# ir2104_V1_1.net
KiCad netlist of a schematic drawn in EasyEDA Pro
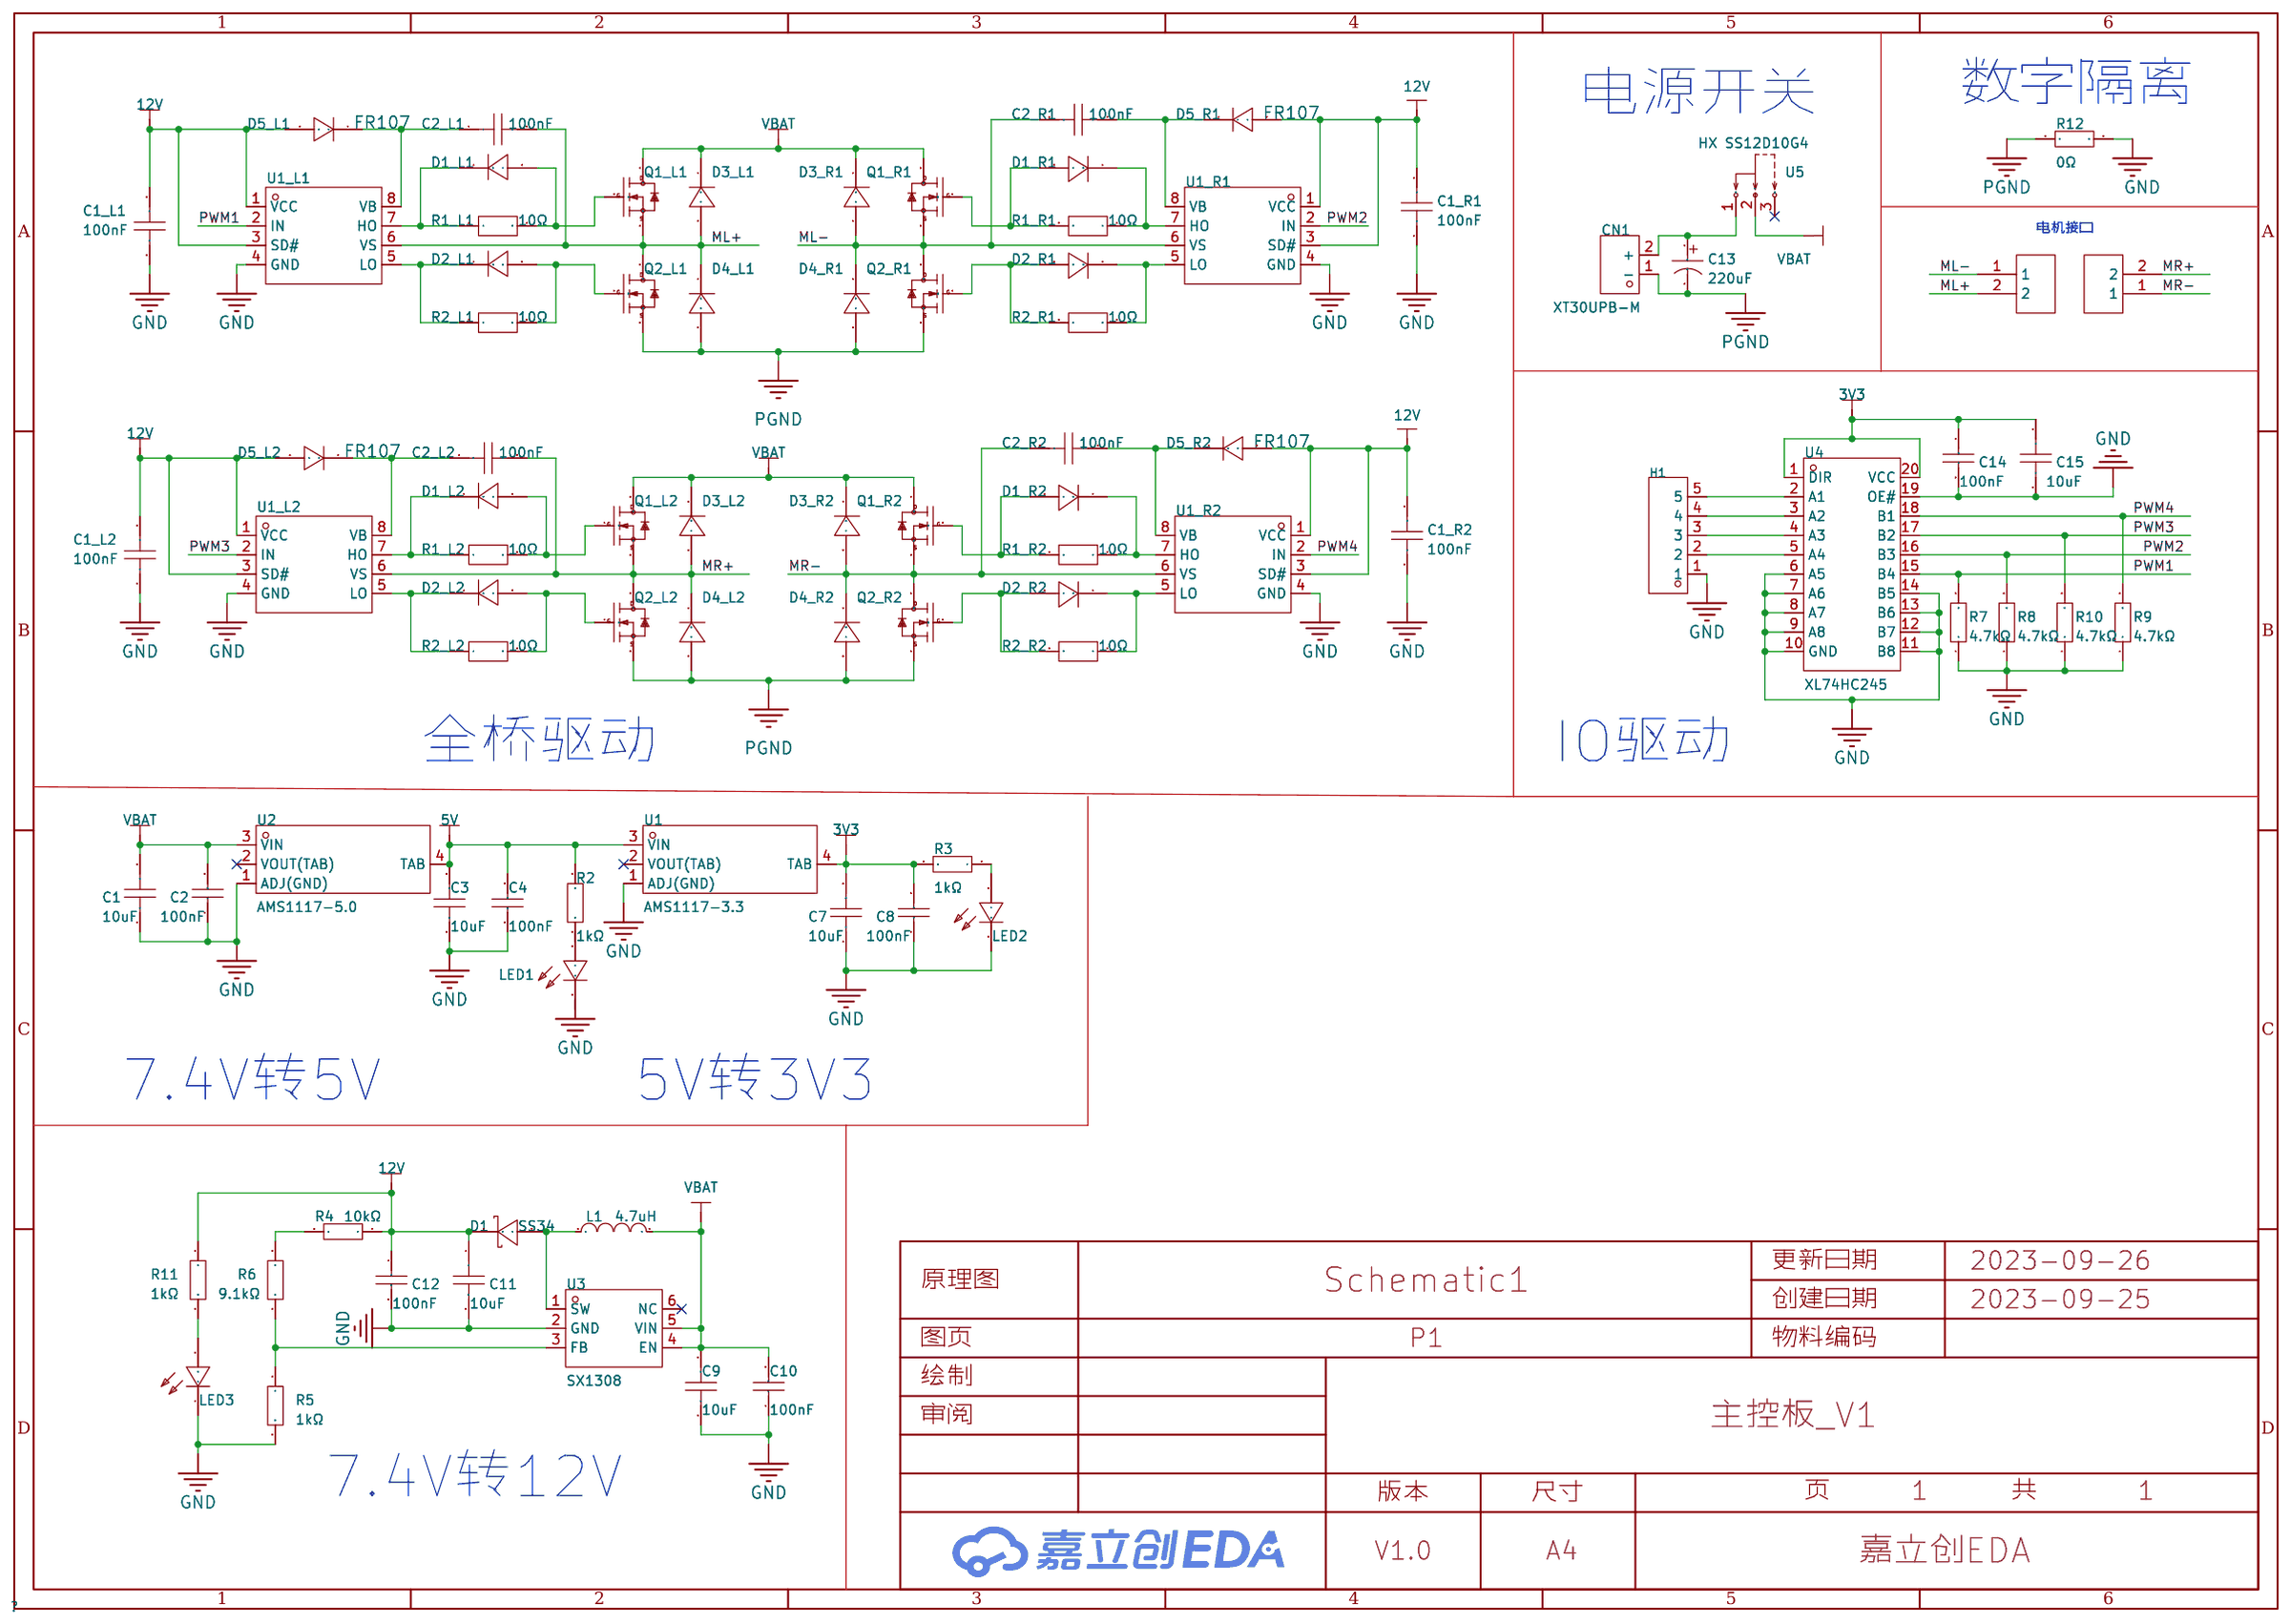
[diagram p0: schematic sheet]

(export (version "E")
  (design (tool "Eeschema 10.0.6"))
  (components
    (comp (ref "C1")
      (value "10uF")
      (footprint "easyedapro:C0603")
      (description "容值:10uF;精度:±20%;额定电压:25V;材质(温度系数):X5R;")
      (fields
        (field (name "Manufacturer Part") "CL10A106MA8NRNC")
        (field (name "Manufacturer") "SAMSUNG(三星)")
      )
      (libsource (lib "easyedapro") (part "CL10A106MA8NRNC"))
    )
    (comp (ref "C1_L1")
      (value "100nF")
      (footprint "easyedapro:C0603")
      (description "容值:100nF;精度:±10%;额定电压:50V;材质(温度系数):X7R;")
      (fields
        (field (name "Manufacturer Part") "CL10B104KB8NNNC")
        (field (name "Manufacturer") "SAMSUNG(三星)")
      )
      (libsource (lib "easyedapro") (part "CL10B104KB8NNNC"))
    )
    (comp (ref "C1_L2")
      (value "100nF")
      (footprint "easyedapro:C0603")
      (description "容值:100nF;精度:±10%;额定电压:50V;材质(温度系数):X7R;")
      (fields
        (field (name "Manufacturer Part") "CL10B104KB8NNNC")
        (field (name "Manufacturer") "SAMSUNG(三星)")
      )
      (libsource (lib "easyedapro") (part "CL10B104KB8NNNC"))
    )
    (comp (ref "C1_R1")
      (value "100nF")
      (footprint "easyedapro:C0603")
      (description "容值:100nF;精度:±10%;额定电压:50V;材质(温度系数):X7R;")
      (fields
        (field (name "Manufacturer Part") "CL10B104KB8NNNC")
        (field (name "Manufacturer") "SAMSUNG(三星)")
      )
      (libsource (lib "easyedapro") (part "CL10B104KB8NNNC"))
    )
    (comp (ref "C1_R2")
      (value "100nF")
      (footprint "easyedapro:C0603")
      (description "容值:100nF;精度:±10%;额定电压:50V;材质(温度系数):X7R;")
      (fields
        (field (name "Manufacturer Part") "CL10B104KB8NNNC")
        (field (name "Manufacturer") "SAMSUNG(三星)")
      )
      (libsource (lib "easyedapro") (part "CL10B104KB8NNNC"))
    )
    (comp (ref "C2")
      (value "100nF")
      (footprint "easyedapro:C0603")
      (description "容值:100nF;精度:±10%;额定电压:50V;材质(温度系数):X7R;")
      (fields (field (name "Manufacturer Part") "0603B104K500NT") (field (name "Manufacturer") "FH(风华)"))
      (libsource (lib "easyedapro") (part "0603B104K500NT"))
    )
    (comp (ref "C2_L1")
      (value "100nF")
      (footprint "easyedapro:C0603")
      (description "容值:100nF;精度:±10%;额定电压:50V;材质(温度系数):X7R;")
      (fields
        (field (name "Manufacturer Part") "CL10B104KB8NNNC")
        (field (name "Manufacturer") "SAMSUNG(三星)")
      )
      (libsource (lib "easyedapro") (part "CL10B104KB8NNNC"))
    )
    (comp (ref "C2_L2")
      (value "100nF")
      (footprint "easyedapro:C0603")
      (description "容值:100nF;精度:±10%;额定电压:50V;材质(温度系数):X7R;")
      (fields
        (field (name "Manufacturer Part") "CL10B104KB8NNNC")
        (field (name "Manufacturer") "SAMSUNG(三星)")
      )
      (libsource (lib "easyedapro") (part "CL10B104KB8NNNC"))
    )
    (comp (ref "C2_R1")
      (value "100nF")
      (footprint "easyedapro:C0603")
      (description "容值:100nF;精度:±10%;额定电压:50V;材质(温度系数):X7R;")
      (fields
        (field (name "Manufacturer Part") "CL10B104KB8NNNC")
        (field (name "Manufacturer") "SAMSUNG(三星)")
      )
      (libsource (lib "easyedapro") (part "CL10B104KB8NNNC"))
    )
    (comp (ref "C2_R2")
      (value "100nF")
      (footprint "easyedapro:C0603")
      (description "容值:100nF;精度:±10%;额定电压:50V;材质(温度系数):X7R;")
      (fields
        (field (name "Manufacturer Part") "CL10B104KB8NNNC")
        (field (name "Manufacturer") "SAMSUNG(三星)")
      )
      (libsource (lib "easyedapro") (part "CL10B104KB8NNNC"))
    )
    (comp (ref "C3")
      (value "10uF")
      (footprint "easyedapro:C0603")
      (description "容值:10uF;精度:±20%;额定电压:25V;材质(温度系数):X5R;")
      (fields
        (field (name "Manufacturer Part") "CL10A106MA8NRNC")
        (field (name "Manufacturer") "SAMSUNG(三星)")
      )
      (libsource (lib "easyedapro") (part "CL10A106MA8NRNC"))
    )
    (comp (ref "C4")
      (value "100nF")
      (footprint "easyedapro:C0603")
      (description "容值:100nF;精度:±10%;额定电压:50V;材质(温度系数):X7R;")
      (fields (field (name "Manufacturer Part") "0603B104K500NT") (field (name "Manufacturer") "FH(风华)"))
      (libsource (lib "easyedapro") (part "0603B104K500NT"))
    )
    (comp (ref "C7")
      (value "10uF")
      (footprint "easyedapro:C0603")
      (description "容值:10uF;精度:±20%;额定电压:25V;材质(温度系数):X5R;")
      (fields
        (field (name "Manufacturer Part") "CL10A106MA8NRNC")
        (field (name "Manufacturer") "SAMSUNG(三星)")
      )
      (libsource (lib "easyedapro") (part "CL10A106MA8NRNC"))
    )
    (comp (ref "C8")
      (value "100nF")
      (footprint "easyedapro:C0603")
      (description "容值:100nF;精度:±10%;额定电压:50V;材质(温度系数):X7R;")
      (fields (field (name "Manufacturer Part") "0603B104K500NT") (field (name "Manufacturer") "FH(风华)"))
      (libsource (lib "easyedapro") (part "0603B104K500NT"))
    )
    (comp (ref "C9")
      (value "10uF")
      (footprint "easyedapro:C0603")
      (description "容值:10uF;精度:±20%;额定电压:25V;材质(温度系数):X5R;")
      (fields
        (field (name "Manufacturer Part") "CL10A106MA8NRNC")
        (field (name "Manufacturer") "SAMSUNG(三星)")
      )
      (libsource (lib "easyedapro") (part "CL10A106MA8NRNC"))
    )
    (comp (ref "C10")
      (value "100nF")
      (footprint "easyedapro:C0603")
      (description "容值:100nF;精度:±10%;额定电压:50V;材质(温度系数):X7R;")
      (fields (field (name "Manufacturer Part") "0603B104K500NT") (field (name "Manufacturer") "FH(风华)"))
      (libsource (lib "easyedapro") (part "0603B104K500NT"))
    )
    (comp (ref "C11")
      (value "10uF")
      (footprint "easyedapro:C0603")
      (description "容值:10uF;精度:±20%;额定电压:25V;材质(温度系数):X5R;")
      (fields
        (field (name "Manufacturer Part") "CL10A106MA8NRNC")
        (field (name "Manufacturer") "SAMSUNG(三星)")
      )
      (libsource (lib "easyedapro") (part "CL10A106MA8NRNC"))
    )
    (comp (ref "C12")
      (value "100nF")
      (footprint "easyedapro:C0603")
      (description "容值:100nF;精度:±10%;额定电压:50V;材质(温度系数):X7R;")
      (fields (field (name "Manufacturer Part") "0603B104K500NT") (field (name "Manufacturer") "FH(风华)"))
      (libsource (lib "easyedapro") (part "0603B104K500NT"))
    )
    (comp (ref "C13")
      (value "220uF")
      (footprint "easyedapro:CAP-TH_BD8.0-P3.50-D0.6-FD")
      (description "容值:220uF;精度:±20%;额定电压:35V;纹波电流:-;等效串联电阻:-;")
      (fields
        (field (name "Manufacturer Part") "KM227M035F12RR0VH2FP0")
        (field (name "Manufacturer") "CX(承兴)")
      )
      (libsource (lib "easyedapro") (part "220uf/35V"))
    )
    (comp (ref "C14")
      (value "100nF")
      (footprint "easyedapro:C0603")
      (description "容值:100nF;精度:±10%;额定电压:50V;材质(温度系数):X7R;")
      (fields (field (name "Manufacturer Part") "0603B104K500NT") (field (name "Manufacturer") "FH(风华)"))
      (libsource (lib "easyedapro") (part "0603B104K500NT"))
    )
    (comp (ref "C15")
      (value "10uF")
      (footprint "easyedapro:C0603")
      (description "容值:10uF;精度:±20%;额定电压:25V;材质(温度系数):X5R;")
      (fields
        (field (name "Manufacturer Part") "CL10A106MA8NRNC")
        (field (name "Manufacturer") "SAMSUNG(三星)")
      )
      (libsource (lib "easyedapro") (part "CL10A106MA8NRNC"))
    )
    (comp (ref "CN1")
      (value "XT30UPB-M")
      (footprint "easyedapro:CONN-TH_XT30UPB-M")
      (fields (field (name "Manufacturer") "AMASS(艾迈斯)"))
      (libsource (lib "easyedapro") (part "XT30UPB-M"))
    )
    (comp (ref "D1")
      (value "SS34")
      (footprint "easyedapro:SMA_L4.3-W2.6-LS5.2-RD")
      (description "二极管配置:独立式;直流反向耐压(Vr):40V;平均整流电流(Io):3A;正向压降(Vf):550mV@3A;")
      (fields (field (name "Manufacturer") "MDD"))
      (libsource (lib "easyedapro") (part "SS34_C8678"))
    )
    (comp (ref "D1_L1")
      (value "US1M")
      (footprint "easyedapro:SMA_L4.4-W2.8-LS5.4-RD")
      (fields (field (name "Manufacturer") "MDD"))
      (libsource (lib "easyedapro") (part "US1MG_C412437"))
    )
    (comp (ref "D1_L2")
      (value "US1M")
      (footprint "easyedapro:SMA_L4.4-W2.8-LS5.4-RD")
      (fields (field (name "Manufacturer") "MDD"))
      (libsource (lib "easyedapro") (part "US1MG_C412437"))
    )
    (comp (ref "D1_R1")
      (value "US1M")
      (footprint "easyedapro:SMA_L4.4-W2.8-LS5.4-RD")
      (fields (field (name "Manufacturer") "MDD"))
      (libsource (lib "easyedapro") (part "US1MG_C412437"))
    )
    (comp (ref "D1_R2")
      (value "US1M")
      (footprint "easyedapro:SMA_L4.4-W2.8-LS5.4-RD")
      (fields (field (name "Manufacturer") "MDD"))
      (libsource (lib "easyedapro") (part "US1MG_C412437"))
    )
    (comp (ref "D2_L1")
      (value "US1M")
      (footprint "easyedapro:SMA_L4.4-W2.8-LS5.4-RD")
      (fields (field (name "Manufacturer") "MDD"))
      (libsource (lib "easyedapro") (part "US1MG_C412437"))
    )
    (comp (ref "D2_L2")
      (value "US1M")
      (footprint "easyedapro:SMA_L4.4-W2.8-LS5.4-RD")
      (fields (field (name "Manufacturer") "MDD"))
      (libsource (lib "easyedapro") (part "US1MG_C412437"))
    )
    (comp (ref "D2_R1")
      (value "US1M")
      (footprint "easyedapro:SMA_L4.4-W2.8-LS5.4-RD")
      (fields (field (name "Manufacturer") "MDD"))
      (libsource (lib "easyedapro") (part "US1MG_C412437"))
    )
    (comp (ref "D2_R2")
      (value "US1M")
      (footprint "easyedapro:SMA_L4.4-W2.8-LS5.4-RD")
      (fields (field (name "Manufacturer") "MDD"))
      (libsource (lib "easyedapro") (part "US1MG_C412437"))
    )
    (comp (ref "D3_L1")
      (value "US1M")
      (footprint "easyedapro:SMA_L4.4-W2.8-LS5.4-RD")
      (fields (field (name "Manufacturer") "MDD"))
      (libsource (lib "easyedapro") (part "US1MG_C412437"))
    )
    (comp (ref "D3_L2")
      (value "US1M")
      (footprint "easyedapro:SMA_L4.4-W2.8-LS5.4-RD")
      (fields (field (name "Manufacturer") "MDD"))
      (libsource (lib "easyedapro") (part "US1MG_C412437"))
    )
    (comp (ref "D3_R1")
      (value "US1M")
      (footprint "easyedapro:SMA_L4.4-W2.8-LS5.4-RD")
      (fields (field (name "Manufacturer") "MDD"))
      (libsource (lib "easyedapro") (part "US1MG_C412437"))
    )
    (comp (ref "D3_R2")
      (value "US1M")
      (footprint "easyedapro:SMA_L4.4-W2.8-LS5.4-RD")
      (fields (field (name "Manufacturer") "MDD"))
      (libsource (lib "easyedapro") (part "US1MG_C412437"))
    )
    (comp (ref "D4_L1")
      (value "US1M")
      (footprint "easyedapro:SMA_L4.4-W2.8-LS5.4-RD")
      (fields (field (name "Manufacturer") "MDD"))
      (libsource (lib "easyedapro") (part "US1MG_C412437"))
    )
    (comp (ref "D4_L2")
      (value "US1M")
      (footprint "easyedapro:SMA_L4.4-W2.8-LS5.4-RD")
      (fields (field (name "Manufacturer") "MDD"))
      (libsource (lib "easyedapro") (part "US1MG_C412437"))
    )
    (comp (ref "D4_R1")
      (value "US1M")
      (footprint "easyedapro:SMA_L4.4-W2.8-LS5.4-RD")
      (fields (field (name "Manufacturer") "MDD"))
      (libsource (lib "easyedapro") (part "US1MG_C412437"))
    )
    (comp (ref "D4_R2")
      (value "US1M")
      (footprint "easyedapro:SMA_L4.4-W2.8-LS5.4-RD")
      (fields (field (name "Manufacturer") "MDD"))
      (libsource (lib "easyedapro") (part "US1MG_C412437"))
    )
    (comp (ref "D5_L1")
      (value "FR107")
      (footprint "easyedapro:SOD-123_L2.8-W1.8-LS3.7-RD")
      (fields (field (name "Manufacturer") "BORN(伯恩半导体)"))
      (libsource (lib "easyedapro") (part "FR107_C511885"))
    )
    (comp (ref "D5_L2")
      (value "FR107")
      (footprint "easyedapro:SOD-123_L2.8-W1.8-LS3.7-RD")
      (fields (field (name "Manufacturer") "BORN(伯恩半导体)"))
      (libsource (lib "easyedapro") (part "FR107_C511885"))
    )
    (comp (ref "D5_R1")
      (value "FR107")
      (footprint "easyedapro:SOD-123_L2.8-W1.8-LS3.7-RD")
      (fields (field (name "Manufacturer") "BORN(伯恩半导体)"))
      (libsource (lib "easyedapro") (part "FR107_C511885"))
    )
    (comp (ref "D5_R2")
      (value "FR107")
      (footprint "easyedapro:SOD-123_L2.8-W1.8-LS3.7-RD")
      (fields (field (name "Manufacturer") "BORN(伯恩半导体)"))
      (libsource (lib "easyedapro") (part "FR107_C511885"))
    )
    (comp (ref "H1")
      (value "PZ254V-11-05P")
      (footprint "easyedapro:HDR-TH_5P-P2.54-V-M")
      (fields (field (name "Manufacturer") "XFCN(兴飞)"))
      (libsource (lib "easyedapro") (part "PZ254V-11-05P"))
    )
    (comp (ref "L1")
      (value "4.7uH")
      (footprint "easyedapro:IND-SMD_L5.4-W5.2_FXL0530")
      (description "电感值:4.7uH;精度:±20%;额定电流:4.5A;饱和电流(Isat):5A;")
      (fields (field (name "Manufacturer Part") "FXL0530-4R7-M") (field (name "Manufacturer") "cjiang(长江微电)"))
      (libsource (lib "easyedapro") (part "FXL0530-4R7-M"))
    )
    (comp (ref "LED1")
      (value "NCD0603R1")
      (footprint "easyedapro:LED0603-RD_RED")
      (description "发光颜色:红灯;")
      (fields (field (name "Manufacturer") "国星光电"))
      (libsource (lib "easyedapro") (part "FC-DA1608HRK-620D"))
    )
    (comp (ref "LED2")
      (value "NCD0603R1")
      (footprint "easyedapro:LED0603-RD_RED")
      (description "发光颜色:红灯;")
      (fields (field (name "Manufacturer") "国星光电"))
      (libsource (lib "easyedapro") (part "FC-DA1608HRK-620D"))
    )
    (comp (ref "LED3")
      (value "NCD0603R1")
      (footprint "easyedapro:LED0603-RD_RED")
      (description "发光颜色:红灯;")
      (fields (field (name "Manufacturer") "国星光电"))
      (libsource (lib "easyedapro") (part "FC-DA1608HRK-620D"))
    )
    (comp (ref "P1")
      (value "WJ500V-5.08-2P")
      (footprint "easyedapro:CONN-TH_2P-P5.00_WJ500V-5.08-2P")
      (fields (field (name "Manufacturer") "KANGNEX(康奈克斯电气)"))
      (libsource (lib "easyedapro") (part "WJ500V-5.08-2P-14-00A"))
    )
    (comp (ref "P2")
      (value "WJ500V-5.08-2P")
      (footprint "easyedapro:CONN-TH_2P-P5.00_WJ500V-5.08-2P")
      (fields (field (name "Manufacturer") "KANGNEX(康奈克斯电气)"))
      (libsource (lib "easyedapro") (part "WJ500V-5.08-2P-14-00A"))
    )
    (comp (ref "Q1_L1")
      (value "IRFR3607TRPBF")
      (footprint "easyedapro:TO-252-3_L6.5-W5.8-P4.58-BL")
      (fields (field (name "Manufacturer") "Infineon(英飞凌)"))
      (libsource (lib "easyedapro") (part "IRFR3607TRPBF"))
    )
    (comp (ref "Q1_L2")
      (value "IRFR3607TRPBF")
      (footprint "easyedapro:TO-252-3_L6.5-W5.8-P4.58-BL")
      (fields (field (name "Manufacturer") "Infineon(英飞凌)"))
      (libsource (lib "easyedapro") (part "IRFR3607TRPBF"))
    )
    (comp (ref "Q1_R1")
      (value "IRFR3607TRPBF")
      (footprint "easyedapro:TO-252-3_L6.5-W5.8-P4.58-BL")
      (fields (field (name "Manufacturer") "Infineon(英飞凌)"))
      (libsource (lib "easyedapro") (part "IRFR3607TRPBF"))
    )
    (comp (ref "Q1_R2")
      (value "IRFR3607TRPBF")
      (footprint "easyedapro:TO-252-3_L6.5-W5.8-P4.58-BL")
      (fields (field (name "Manufacturer") "Infineon(英飞凌)"))
      (libsource (lib "easyedapro") (part "IRFR3607TRPBF"))
    )
    (comp (ref "Q2_L1")
      (value "IRFR3607TRPBF")
      (footprint "easyedapro:TO-252-3_L6.5-W5.8-P4.58-BL")
      (fields (field (name "Manufacturer") "Infineon(英飞凌)"))
      (libsource (lib "easyedapro") (part "IRFR3607TRPBF"))
    )
    (comp (ref "Q2_L2")
      (value "IRFR3607TRPBF")
      (footprint "easyedapro:TO-252-3_L6.5-W5.8-P4.58-BL")
      (fields (field (name "Manufacturer") "Infineon(英飞凌)"))
      (libsource (lib "easyedapro") (part "IRFR3607TRPBF"))
    )
    (comp (ref "Q2_R1")
      (value "IRFR3607TRPBF")
      (footprint "easyedapro:TO-252-3_L6.5-W5.8-P4.58-BL")
      (fields (field (name "Manufacturer") "Infineon(英飞凌)"))
      (libsource (lib "easyedapro") (part "IRFR3607TRPBF"))
    )
    (comp (ref "Q2_R2")
      (value "IRFR3607TRPBF")
      (footprint "easyedapro:TO-252-3_L6.5-W5.8-P4.58-BL")
      (fields (field (name "Manufacturer") "Infineon(英飞凌)"))
      (libsource (lib "easyedapro") (part "IRFR3607TRPBF"))
    )
    (comp (ref "R1_L1")
      (value "10Ω")
      (footprint "easyedapro:R0603")
      (description "阻值:10Ω;精度:±0.5%;功率:250mW;")
      (fields (field (name "Manufacturer Part") "ERJUP3D10R0V") (field (name "Manufacturer") "PANASONIC(松下)"))
      (libsource (lib "easyedapro") (part "ERJUP3D10R0V"))
    )
    (comp (ref "R1_L2")
      (value "10Ω")
      (footprint "easyedapro:R0603")
      (description "阻值:10Ω;精度:±0.5%;功率:250mW;")
      (fields (field (name "Manufacturer Part") "ERJUP3D10R0V") (field (name "Manufacturer") "PANASONIC(松下)"))
      (libsource (lib "easyedapro") (part "ERJUP3D10R0V"))
    )
    (comp (ref "R1_R1")
      (value "10Ω")
      (footprint "easyedapro:R0603")
      (description "阻值:10Ω;精度:±0.5%;功率:250mW;")
      (fields (field (name "Manufacturer Part") "ERJUP3D10R0V") (field (name "Manufacturer") "PANASONIC(松下)"))
      (libsource (lib "easyedapro") (part "ERJUP3D10R0V"))
    )
    (comp (ref "R1_R2")
      (value "10Ω")
      (footprint "easyedapro:R0603")
      (description "阻值:10Ω;精度:±0.5%;功率:250mW;")
      (fields (field (name "Manufacturer Part") "ERJUP3D10R0V") (field (name "Manufacturer") "PANASONIC(松下)"))
      (libsource (lib "easyedapro") (part "ERJUP3D10R0V"))
    )
    (comp (ref "R2")
      (value "1kΩ")
      (footprint "easyedapro:R0603")
      (description "电阻类型:厚膜电阻;阻值:1kΩ;精度:±1%;功率:100mW;")
      (fields
        (field (name "Manufacturer Part") "0603WAF1001T5E")
        (field (name "Manufacturer") "UNI-ROYAL(厚声)")
      )
      (libsource (lib "easyedapro") (part "0603WAF1001T5E"))
    )
    (comp (ref "R2_L1")
      (value "10Ω")
      (footprint "easyedapro:R0603")
      (description "阻值:10Ω;精度:±0.5%;功率:250mW;")
      (fields (field (name "Manufacturer Part") "ERJUP3D10R0V") (field (name "Manufacturer") "PANASONIC(松下)"))
      (libsource (lib "easyedapro") (part "ERJUP3D10R0V"))
    )
    (comp (ref "R2_L2")
      (value "10Ω")
      (footprint "easyedapro:R0603")
      (description "阻值:10Ω;精度:±0.5%;功率:250mW;")
      (fields (field (name "Manufacturer Part") "ERJUP3D10R0V") (field (name "Manufacturer") "PANASONIC(松下)"))
      (libsource (lib "easyedapro") (part "ERJUP3D10R0V"))
    )
    (comp (ref "R2_R1")
      (value "10Ω")
      (footprint "easyedapro:R0603")
      (description "阻值:10Ω;精度:±0.5%;功率:250mW;")
      (fields (field (name "Manufacturer Part") "ERJUP3D10R0V") (field (name "Manufacturer") "PANASONIC(松下)"))
      (libsource (lib "easyedapro") (part "ERJUP3D10R0V"))
    )
    (comp (ref "R2_R2")
      (value "10Ω")
      (footprint "easyedapro:R0603")
      (description "阻值:10Ω;精度:±0.5%;功率:250mW;")
      (fields (field (name "Manufacturer Part") "ERJUP3D10R0V") (field (name "Manufacturer") "PANASONIC(松下)"))
      (libsource (lib "easyedapro") (part "ERJUP3D10R0V"))
    )
    (comp (ref "R3")
      (value "1kΩ")
      (footprint "easyedapro:R0603")
      (description "电阻类型:厚膜电阻;阻值:1kΩ;精度:±1%;功率:100mW;")
      (fields
        (field (name "Manufacturer Part") "0603WAF1001T5E")
        (field (name "Manufacturer") "UNI-ROYAL(厚声)")
      )
      (libsource (lib "easyedapro") (part "0603WAF1001T5E"))
    )
    (comp (ref "R4")
      (value "10kΩ")
      (footprint "easyedapro:R0603")
      (description "电阻类型:薄膜电阻;阻值:10kΩ;精度:±0.1%;功率:100mW;")
      (fields (field (name "Manufacturer Part") "RT0603BRD0710KL") (field (name "Manufacturer") "YAGEO(国巨)"))
      (libsource (lib "easyedapro") (part "RT0603BRD0710KL"))
    )
    (comp (ref "R5")
      (value "1kΩ")
      (footprint "easyedapro:R0603")
      (description "电阻类型:薄膜电阻;阻值:1kΩ;精度:±0.1%;功率:100mW;")
      (fields (field (name "Manufacturer Part") "RT0603BRD071KL") (field (name "Manufacturer") "YAGEO(国巨)"))
      (libsource (lib "easyedapro") (part "RT0603BRD071KL"))
    )
    (comp (ref "R6")
      (value "9.1kΩ")
      (footprint "easyedapro:R0603")
      (description "电阻类型:薄膜电阻;阻值:9.1kΩ;精度:±0.1%;功率:100mW;")
      (fields (field (name "Manufacturer Part") "PTFR0603B9K10P9") (field (name "Manufacturer") "RESI(开步睿思）"))
      (libsource (lib "easyedapro") (part "PTFR0603B9K10P9"))
    )
    (comp (ref "R7")
      (value "4.7kΩ")
      (footprint "easyedapro:R0603")
      (description "电阻类型:厚膜电阻;阻值:4.7kΩ;精度:±1%;功率:100mW;")
      (fields
        (field (name "Manufacturer Part") "0603WAF4701T5E")
        (field (name "Manufacturer") "UNI-ROYAL(厚声)")
      )
      (libsource (lib "easyedapro") (part "0603WAF4701T5E"))
    )
    (comp (ref "R8")
      (value "4.7kΩ")
      (footprint "easyedapro:R0603")
      (description "电阻类型:厚膜电阻;阻值:4.7kΩ;精度:±1%;功率:100mW;")
      (fields
        (field (name "Manufacturer Part") "0603WAF4701T5E")
        (field (name "Manufacturer") "UNI-ROYAL(厚声)")
      )
      (libsource (lib "easyedapro") (part "0603WAF4701T5E"))
    )
    (comp (ref "R9")
      (value "4.7kΩ")
      (footprint "easyedapro:R0603")
      (description "电阻类型:厚膜电阻;阻值:4.7kΩ;精度:±1%;功率:100mW;")
      (fields
        (field (name "Manufacturer Part") "0603WAF4701T5E")
        (field (name "Manufacturer") "UNI-ROYAL(厚声)")
      )
      (libsource (lib "easyedapro") (part "0603WAF4701T5E"))
    )
    (comp (ref "R10")
      (value "4.7kΩ")
      (footprint "easyedapro:R0603")
      (description "电阻类型:厚膜电阻;阻值:4.7kΩ;精度:±1%;功率:100mW;")
      (fields
        (field (name "Manufacturer Part") "0603WAF4701T5E")
        (field (name "Manufacturer") "UNI-ROYAL(厚声)")
      )
      (libsource (lib "easyedapro") (part "0603WAF4701T5E"))
    )
    (comp (ref "R11")
      (value "1kΩ")
      (footprint "easyedapro:R0603")
      (description "电阻类型:厚膜电阻;阻值:1kΩ;精度:±1%;功率:100mW;")
      (fields
        (field (name "Manufacturer Part") "0603WAF1001T5E")
        (field (name "Manufacturer") "UNI-ROYAL(厚声)")
      )
      (libsource (lib "easyedapro") (part "0603WAF1001T5E"))
    )
    (comp (ref "R12")
      (value "0Ω")
      (footprint "easyedapro:R0805")
      (description "电阻类型:厚膜电阻;阻值:0Ω;精度:±1%;功率:125mW;")
      (fields
        (field (name "Manufacturer Part") "0805W8F0000T5E")
        (field (name "Manufacturer") "UNI-ROYAL(厚声)")
      )
      (libsource (lib "easyedapro") (part "0805W8F0000T5E"))
    )
    (comp (ref "U1")
      (value "AMS1117-3.3")
      (footprint "easyedapro:SOT-223-4_L6.5-W3.5-P2.30-LS7.0-BR")
      (description "输出类型:固定;输出极性:正;最大输入电压:18V;输出电压:3.3V;输出电流:1A;电源纹波抑制比(PSRR):60dB@(120Hz);")
      (fields (field (name "Manufacturer") "UMW(广东友台半导体)"))
      (libsource (lib "easyedapro") (part "AMS1117-3.3_C347222"))
    )
    (comp (ref "U1_L1")
      (value "EG2104")
      (footprint "easyedapro:SOP-8_L5.0-W4.0-P1.27-LS6.2-BL")
      (description "高性价比, 600V，半桥式Nmos预驱动器")
      (fields (field (name "Manufacturer") "EG(屹晶微)"))
      (libsource (lib "easyedapro") (part "EG2104"))
    )
    (comp (ref "U1_L2")
      (value "EG2104")
      (footprint "easyedapro:SOP-8_L5.0-W4.0-P1.27-LS6.2-BL")
      (description "高性价比, 600V，半桥式Nmos预驱动器")
      (fields (field (name "Manufacturer") "EG(屹晶微)"))
      (libsource (lib "easyedapro") (part "EG2104"))
    )
    (comp (ref "U1_R1")
      (value "EG2104")
      (footprint "easyedapro:SOP-8_L5.0-W4.0-P1.27-LS6.2-BL")
      (description "高性价比, 600V，半桥式Nmos预驱动器")
      (fields (field (name "Manufacturer") "EG(屹晶微)"))
      (libsource (lib "easyedapro") (part "EG2104"))
    )
    (comp (ref "U1_R2")
      (value "EG2104")
      (footprint "easyedapro:SOP-8_L5.0-W4.0-P1.27-LS6.2-BL")
      (description "高性价比, 600V，半桥式Nmos预驱动器")
      (fields (field (name "Manufacturer") "EG(屹晶微)"))
      (libsource (lib "easyedapro") (part "EG2104"))
    )
    (comp (ref "U2")
      (value "AMS1117-5.0")
      (footprint "easyedapro:SOT-223_L6.7-W3.5-P2.30-BR")
      (description "输出类型:固定;输出极性:正;最大输入电压:18V;输出电压:5V;输出电流:1A;电源纹波抑制比(PSRR):60dB@(120Hz);")
      (fields (field (name "Manufacturer") "UMW(广东友台半导体)"))
      (libsource (lib "easyedapro") (part "AMS1117-5.0_C347223"))
    )
    (comp (ref "U3")
      (value "SX1308")
      (footprint "easyedapro:SOT-23-6_L2.9-W1.6-P0.95-LS2.8-BL")
      (description "功能类型:升压型;同步整流:否;输出通道数:1;拓扑结构:升压式;输入电压:2V~24V;输出电压:28V;输出电流(最大值):-;开关频率:1.2MHz;")
      (fields (field (name "Manufacturer") "SX(硕芯科技)"))
      (libsource (lib "easyedapro") (part "SX1308"))
    )
    (comp (ref "U4")
      (value "XL74HC245")
      (footprint "easyedapro:SOP-20_L12.8-W7.5-P1.27-LS10.4-BL")
      (description "八路总线收发器")
      (fields (field (name "Manufacturer") "XINLUDA(信路达)"))
      (libsource (lib "easyedapro") (part "XL74HC245"))
    )
    (comp (ref "U5")
      (value "HX SS12D10G4")
      (footprint "easyedapro:SW-TH_SHOU-HAN_SS12D10G4")
      (fields (field (name "Manufacturer") "hanxia(韩下)"))
      (libsource (lib "easyedapro") (part "HX SS12D10G4"))
    )
  )
  (nets
    (net (code "1") (name "/ML+") (class "Default")
      (node (ref "C2_L1") (pin "2") (pinfunction "2_2") (pintype "input"))
      (node (ref "D3_L1") (pin "2") (pinfunction "A_2") (pintype "input"))
      (node (ref "D4_L1") (pin "1") (pinfunction "C_1") (pintype "input"))
      (node (ref "P1") (pin "2") (pinfunction "2_2") (pintype "input"))
      (node (ref "Q1_L1") (pin "3") (pinfunction "S_3") (pintype "input"))
      (node (ref "Q2_L1") (pin "2") (pinfunction "D_2") (pintype "input"))
      (node (ref "U1_L1") (pin "6") (pinfunction "VS_6") (pintype "input"))
    )
    (net (code "2") (name "/ML-") (class "Default")
      (node (ref "C2_R1") (pin "2") (pinfunction "2_2") (pintype "input"))
      (node (ref "D3_R1") (pin "2") (pinfunction "A_2") (pintype "input"))
      (node (ref "D4_R1") (pin "1") (pinfunction "C_1") (pintype "input"))
      (node (ref "P1") (pin "1") (pinfunction "1_1") (pintype "input"))
      (node (ref "Q1_R1") (pin "3") (pinfunction "S_3") (pintype "input"))
      (node (ref "Q2_R1") (pin "2") (pinfunction "D_2") (pintype "input"))
      (node (ref "U1_R1") (pin "6") (pinfunction "VS_6") (pintype "input"))
    )
    (net (code "3") (name "/MR+") (class "Default")
      (node (ref "C2_L2") (pin "2") (pinfunction "2_2") (pintype "input"))
      (node (ref "D3_L2") (pin "2") (pinfunction "A_2") (pintype "input"))
      (node (ref "D4_L2") (pin "1") (pinfunction "C_1") (pintype "input"))
      (node (ref "P2") (pin "2") (pinfunction "2_2") (pintype "input"))
      (node (ref "Q1_L2") (pin "3") (pinfunction "S_3") (pintype "input"))
      (node (ref "Q2_L2") (pin "2") (pinfunction "D_2") (pintype "input"))
      (node (ref "U1_L2") (pin "6") (pinfunction "VS_6") (pintype "input"))
    )
    (net (code "4") (name "/MR-") (class "Default")
      (node (ref "C2_R2") (pin "2") (pinfunction "2_2") (pintype "input"))
      (node (ref "D3_R2") (pin "2") (pinfunction "A_2") (pintype "input"))
      (node (ref "D4_R2") (pin "1") (pinfunction "C_1") (pintype "input"))
      (node (ref "P2") (pin "1") (pinfunction "1_1") (pintype "input"))
      (node (ref "Q1_R2") (pin "3") (pinfunction "S_3") (pintype "input"))
      (node (ref "Q2_R2") (pin "2") (pinfunction "D_2") (pintype "input"))
      (node (ref "U1_R2") (pin "6") (pinfunction "VS_6") (pintype "input"))
    )
    (net (code "5") (name "/PWM1") (class "Default")
      (node (ref "R7") (pin "2") (pinfunction "2_2") (pintype "input"))
      (node (ref "U1_L1") (pin "2") (pinfunction "IN_2") (pintype "input"))
      (node (ref "U4") (pin "15") (pinfunction "B4_15") (pintype "input"))
    )
    (net (code "6") (name "/PWM2") (class "Default")
      (node (ref "R8") (pin "2") (pinfunction "2_2") (pintype "input"))
      (node (ref "U1_R1") (pin "2") (pinfunction "IN_2") (pintype "input"))
      (node (ref "U4") (pin "16") (pinfunction "B3_16") (pintype "input"))
    )
    (net (code "7") (name "/PWM3") (class "Default")
      (node (ref "R10") (pin "2") (pinfunction "2_2") (pintype "input"))
      (node (ref "U1_L2") (pin "2") (pinfunction "IN_2") (pintype "input"))
      (node (ref "U4") (pin "17") (pinfunction "B2_17") (pintype "input"))
    )
    (net (code "8") (name "/PWM4") (class "Default")
      (node (ref "R9") (pin "2") (pinfunction "2_2") (pintype "input"))
      (node (ref "U1_R2") (pin "2") (pinfunction "IN_2") (pintype "input"))
      (node (ref "U4") (pin "18") (pinfunction "B1_18") (pintype "input"))
    )
    (net (code "9") (name "3V3") (class "Default")
      (node (ref "C14") (pin "1") (pinfunction "1_1") (pintype "input"))
      (node (ref "C15") (pin "1") (pinfunction "1_1") (pintype "input"))
      (node (ref "C7") (pin "2") (pinfunction "2_2") (pintype "input"))
      (node (ref "C8") (pin "2") (pinfunction "2_2") (pintype "input"))
      (node (ref "R3") (pin "2") (pinfunction "2_2") (pintype "input"))
      (node (ref "U1") (pin "4") (pinfunction "TAB_4") (pintype "input"))
      (node (ref "U4") (pin "1") (pinfunction "DIR_1") (pintype "input"))
      (node (ref "U4") (pin "20") (pinfunction "VCC_20") (pintype "input"))
    )
    (net (code "10") (name "5V") (class "Default")
      (node (ref "C3") (pin "2") (pinfunction "2_2") (pintype "input"))
      (node (ref "C4") (pin "2") (pinfunction "2_2") (pintype "input"))
      (node (ref "R2") (pin "1") (pinfunction "1_1") (pintype "input"))
      (node (ref "U1") (pin "3") (pinfunction "VIN_3") (pintype "input"))
      (node (ref "U2") (pin "4") (pinfunction "TAB_4") (pintype "input"))
    )
    (net (code "11") (name "12V") (class "Default")
      (node (ref "C11") (pin "1") (pinfunction "1_1") (pintype "input"))
      (node (ref "C12") (pin "1") (pinfunction "1_1") (pintype "input"))
      (node (ref "C1_L1") (pin "2") (pinfunction "2_2") (pintype "input"))
      (node (ref "C1_L2") (pin "2") (pinfunction "2_2") (pintype "input"))
      (node (ref "C1_R1") (pin "2") (pinfunction "2_2") (pintype "input"))
      (node (ref "C1_R2") (pin "2") (pinfunction "2_2") (pintype "input"))
      (node (ref "D1") (pin "1") (pinfunction "K_1") (pintype "input"))
      (node (ref "D5_L1") (pin "2") (pinfunction "A_2") (pintype "input"))
      (node (ref "D5_L2") (pin "2") (pinfunction "A_2") (pintype "input"))
      (node (ref "D5_R1") (pin "2") (pinfunction "A_2") (pintype "input"))
      (node (ref "D5_R2") (pin "2") (pinfunction "A_2") (pintype "input"))
      (node (ref "R11") (pin "1") (pinfunction "1_1") (pintype "input"))
      (node (ref "R4") (pin "1") (pinfunction "1_1") (pintype "input"))
      (node (ref "U1_L1") (pin "1") (pinfunction "VCC_1") (pintype "input"))
      (node (ref "U1_L1") (pin "3") (pinfunction "SD#_3") (pintype "input"))
      (node (ref "U1_L2") (pin "1") (pinfunction "VCC_1") (pintype "input"))
      (node (ref "U1_L2") (pin "3") (pinfunction "SD#_3") (pintype "input"))
      (node (ref "U1_R1") (pin "1") (pinfunction "VCC_1") (pintype "input"))
      (node (ref "U1_R1") (pin "3") (pinfunction "SD#_3") (pintype "input"))
      (node (ref "U1_R2") (pin "1") (pinfunction "VCC_1") (pintype "input"))
      (node (ref "U1_R2") (pin "3") (pinfunction "SD#_3") (pintype "input"))
    )
    (net (code "12") (name "GND") (class "Default")
      (node (ref "C1") (pin "1") (pinfunction "1_1") (pintype "input"))
      (node (ref "C10") (pin "1") (pinfunction "1_1") (pintype "input"))
      (node (ref "C11") (pin "2") (pinfunction "2_2") (pintype "input"))
      (node (ref "C12") (pin "2") (pinfunction "2_2") (pintype "input"))
      (node (ref "C14") (pin "2") (pinfunction "2_2") (pintype "input"))
      (node (ref "C15") (pin "2") (pinfunction "2_2") (pintype "input"))
      (node (ref "C1_L1") (pin "1") (pinfunction "1_1") (pintype "input"))
      (node (ref "C1_L2") (pin "1") (pinfunction "1_1") (pintype "input"))
      (node (ref "C1_R1") (pin "1") (pinfunction "1_1") (pintype "input"))
      (node (ref "C1_R2") (pin "1") (pinfunction "1_1") (pintype "input"))
      (node (ref "C2") (pin "1") (pinfunction "1_1") (pintype "input"))
      (node (ref "C3") (pin "1") (pinfunction "1_1") (pintype "input"))
      (node (ref "C4") (pin "1") (pinfunction "1_1") (pintype "input"))
      (node (ref "C7") (pin "1") (pinfunction "1_1") (pintype "input"))
      (node (ref "C8") (pin "1") (pinfunction "1_1") (pintype "input"))
      (node (ref "C9") (pin "1") (pinfunction "1_1") (pintype "input"))
      (node (ref "H1") (pin "1") (pinfunction "1_1") (pintype "input"))
      (node (ref "LED1") (pin "1") (pinfunction "K_1") (pintype "input"))
      (node (ref "LED2") (pin "1") (pinfunction "K_1") (pintype "input"))
      (node (ref "LED3") (pin "1") (pinfunction "K_1") (pintype "input"))
      (node (ref "R10") (pin "1") (pinfunction "1_1") (pintype "input"))
      (node (ref "R12") (pin "2") (pinfunction "2_2") (pintype "input"))
      (node (ref "R5") (pin "2") (pinfunction "2_2") (pintype "input"))
      (node (ref "R7") (pin "1") (pinfunction "1_1") (pintype "input"))
      (node (ref "R8") (pin "1") (pinfunction "1_1") (pintype "input"))
      (node (ref "R9") (pin "1") (pinfunction "1_1") (pintype "input"))
      (node (ref "U1") (pin "1") (pinfunction "ADJ(GND)_1") (pintype "input"))
      (node (ref "U1_L1") (pin "4") (pinfunction "GND_4") (pintype "input"))
      (node (ref "U1_L2") (pin "4") (pinfunction "GND_4") (pintype "input"))
      (node (ref "U1_R1") (pin "4") (pinfunction "GND_4") (pintype "input"))
      (node (ref "U1_R2") (pin "4") (pinfunction "GND_4") (pintype "input"))
      (node (ref "U2") (pin "1") (pinfunction "ADJ(GND)_1") (pintype "input"))
      (node (ref "U3") (pin "2") (pinfunction "GND_2") (pintype "input"))
      (node (ref "U4") (pin "10") (pinfunction "GND_10") (pintype "input"))
      (node (ref "U4") (pin "11") (pinfunction "B8_11") (pintype "input"))
      (node (ref "U4") (pin "12") (pinfunction "B7_12") (pintype "input"))
      (node (ref "U4") (pin "13") (pinfunction "B6_13") (pintype "input"))
      (node (ref "U4") (pin "14") (pinfunction "B5_14") (pintype "input"))
      (node (ref "U4") (pin "19") (pinfunction "OE#_19") (pintype "input"))
      (node (ref "U4") (pin "6") (pinfunction "A5_6") (pintype "input"))
      (node (ref "U4") (pin "7") (pinfunction "A6_7") (pintype "input"))
      (node (ref "U4") (pin "8") (pinfunction "A7_8") (pintype "input"))
      (node (ref "U4") (pin "9") (pinfunction "A8_9") (pintype "input"))
    )
    (net (code "13") (name "Net-(CN1-+)") (class "Default")
      (node (ref "C13") (pin "1") (pinfunction "1_1") (pintype "input"))
      (node (ref "CN1") (pin "2") (pinfunction "+_2") (pintype "input"))
      (node (ref "U5") (pin "1") (pinfunction "1_1") (pintype "input"))
    )
    (net (code "14") (name "Net-(D1-A)") (class "Default")
      (node (ref "D1") (pin "2") (pinfunction "A_2") (pintype "input"))
      (node (ref "L1") (pin "1") (pinfunction "1_1") (pintype "input"))
      (node (ref "U3") (pin "1") (pinfunction "SW_1") (pintype "input"))
    )
    (net (code "15") (name "Net-(D1_L1-A)") (class "Default")
      (node (ref "D1_L1") (pin "2") (pinfunction "A_2") (pintype "input"))
      (node (ref "Q1_L1") (pin "1") (pinfunction "G_1") (pintype "input"))
      (node (ref "R1_L1") (pin "2") (pinfunction "2_2") (pintype "input"))
    )
    (net (code "16") (name "Net-(D1_L1-C)") (class "Default")
      (node (ref "D1_L1") (pin "1") (pinfunction "C_1") (pintype "input"))
      (node (ref "R1_L1") (pin "1") (pinfunction "1_1") (pintype "input"))
      (node (ref "U1_L1") (pin "7") (pinfunction "HO_7") (pintype "input"))
    )
    (net (code "17") (name "Net-(D1_L2-A)") (class "Default")
      (node (ref "D1_L2") (pin "2") (pinfunction "A_2") (pintype "input"))
      (node (ref "Q1_L2") (pin "1") (pinfunction "G_1") (pintype "input"))
      (node (ref "R1_L2") (pin "2") (pinfunction "2_2") (pintype "input"))
    )
    (net (code "18") (name "Net-(D1_L2-C)") (class "Default")
      (node (ref "D1_L2") (pin "1") (pinfunction "C_1") (pintype "input"))
      (node (ref "R1_L2") (pin "1") (pinfunction "1_1") (pintype "input"))
      (node (ref "U1_L2") (pin "7") (pinfunction "HO_7") (pintype "input"))
    )
    (net (code "19") (name "Net-(D1_R1-A)") (class "Default")
      (node (ref "D1_R1") (pin "2") (pinfunction "A_2") (pintype "input"))
      (node (ref "Q1_R1") (pin "1") (pinfunction "G_1") (pintype "input"))
      (node (ref "R1_R1") (pin "2") (pinfunction "2_2") (pintype "input"))
    )
    (net (code "20") (name "Net-(D1_R1-C)") (class "Default")
      (node (ref "D1_R1") (pin "1") (pinfunction "C_1") (pintype "input"))
      (node (ref "R1_R1") (pin "1") (pinfunction "1_1") (pintype "input"))
      (node (ref "U1_R1") (pin "7") (pinfunction "HO_7") (pintype "input"))
    )
    (net (code "21") (name "Net-(D1_R2-A)") (class "Default")
      (node (ref "D1_R2") (pin "2") (pinfunction "A_2") (pintype "input"))
      (node (ref "Q1_R2") (pin "1") (pinfunction "G_1") (pintype "input"))
      (node (ref "R1_R2") (pin "2") (pinfunction "2_2") (pintype "input"))
    )
    (net (code "22") (name "Net-(D1_R2-C)") (class "Default")
      (node (ref "D1_R2") (pin "1") (pinfunction "C_1") (pintype "input"))
      (node (ref "R1_R2") (pin "1") (pinfunction "1_1") (pintype "input"))
      (node (ref "U1_R2") (pin "7") (pinfunction "HO_7") (pintype "input"))
    )
    (net (code "23") (name "Net-(D2_L1-A)") (class "Default")
      (node (ref "D2_L1") (pin "2") (pinfunction "A_2") (pintype "input"))
      (node (ref "Q2_L1") (pin "1") (pinfunction "G_1") (pintype "input"))
      (node (ref "R2_L1") (pin "2") (pinfunction "2_2") (pintype "input"))
    )
    (net (code "24") (name "Net-(D2_L1-C)") (class "Default")
      (node (ref "D2_L1") (pin "1") (pinfunction "C_1") (pintype "input"))
      (node (ref "R2_L1") (pin "1") (pinfunction "1_1") (pintype "input"))
      (node (ref "U1_L1") (pin "5") (pinfunction "LO_5") (pintype "input"))
    )
    (net (code "25") (name "Net-(D2_L2-A)") (class "Default")
      (node (ref "D2_L2") (pin "2") (pinfunction "A_2") (pintype "input"))
      (node (ref "Q2_L2") (pin "1") (pinfunction "G_1") (pintype "input"))
      (node (ref "R2_L2") (pin "2") (pinfunction "2_2") (pintype "input"))
    )
    (net (code "26") (name "Net-(D2_L2-C)") (class "Default")
      (node (ref "D2_L2") (pin "1") (pinfunction "C_1") (pintype "input"))
      (node (ref "R2_L2") (pin "1") (pinfunction "1_1") (pintype "input"))
      (node (ref "U1_L2") (pin "5") (pinfunction "LO_5") (pintype "input"))
    )
    (net (code "27") (name "Net-(D2_R1-A)") (class "Default")
      (node (ref "D2_R1") (pin "2") (pinfunction "A_2") (pintype "input"))
      (node (ref "Q2_R1") (pin "1") (pinfunction "G_1") (pintype "input"))
      (node (ref "R2_R1") (pin "2") (pinfunction "2_2") (pintype "input"))
    )
    (net (code "28") (name "Net-(D2_R1-C)") (class "Default")
      (node (ref "D2_R1") (pin "1") (pinfunction "C_1") (pintype "input"))
      (node (ref "R2_R1") (pin "1") (pinfunction "1_1") (pintype "input"))
      (node (ref "U1_R1") (pin "5") (pinfunction "LO_5") (pintype "input"))
    )
    (net (code "29") (name "Net-(D2_R2-A)") (class "Default")
      (node (ref "D2_R2") (pin "2") (pinfunction "A_2") (pintype "input"))
      (node (ref "Q2_R2") (pin "1") (pinfunction "G_1") (pintype "input"))
      (node (ref "R2_R2") (pin "2") (pinfunction "2_2") (pintype "input"))
    )
    (net (code "30") (name "Net-(D2_R2-C)") (class "Default")
      (node (ref "D2_R2") (pin "1") (pinfunction "C_1") (pintype "input"))
      (node (ref "R2_R2") (pin "1") (pinfunction "1_1") (pintype "input"))
      (node (ref "U1_R2") (pin "5") (pinfunction "LO_5") (pintype "input"))
    )
    (net (code "31") (name "Net-(D5_L1-K)") (class "Default")
      (node (ref "C2_L1") (pin "1") (pinfunction "1_1") (pintype "input"))
      (node (ref "D5_L1") (pin "1") (pinfunction "K_1") (pintype "input"))
      (node (ref "U1_L1") (pin "8") (pinfunction "VB_8") (pintype "input"))
    )
    (net (code "32") (name "Net-(D5_L2-K)") (class "Default")
      (node (ref "C2_L2") (pin "1") (pinfunction "1_1") (pintype "input"))
      (node (ref "D5_L2") (pin "1") (pinfunction "K_1") (pintype "input"))
      (node (ref "U1_L2") (pin "8") (pinfunction "VB_8") (pintype "input"))
    )
    (net (code "33") (name "Net-(D5_R1-K)") (class "Default")
      (node (ref "C2_R1") (pin "1") (pinfunction "1_1") (pintype "input"))
      (node (ref "D5_R1") (pin "1") (pinfunction "K_1") (pintype "input"))
      (node (ref "U1_R1") (pin "8") (pinfunction "VB_8") (pintype "input"))
    )
    (net (code "34") (name "Net-(D5_R2-K)") (class "Default")
      (node (ref "C2_R2") (pin "1") (pinfunction "1_1") (pintype "input"))
      (node (ref "D5_R2") (pin "1") (pinfunction "K_1") (pintype "input"))
      (node (ref "U1_R2") (pin "8") (pinfunction "VB_8") (pintype "input"))
    )
    (net (code "35") (name "Net-(LED1-A)") (class "Default")
      (node (ref "LED1") (pin "2") (pinfunction "A_2") (pintype "input"))
      (node (ref "R2") (pin "2") (pinfunction "2_2") (pintype "input"))
    )
    (net (code "36") (name "Net-(LED2-A)") (class "Default")
      (node (ref "LED2") (pin "2") (pinfunction "A_2") (pintype "input"))
      (node (ref "R3") (pin "1") (pinfunction "1_1") (pintype "input"))
    )
    (net (code "37") (name "Net-(LED3-A)") (class "Default")
      (node (ref "LED3") (pin "2") (pinfunction "A_2") (pintype "input"))
      (node (ref "R11") (pin "2") (pinfunction "2_2") (pintype "input"))
    )
    (net (code "38") (name "Net-(R4-Pad2)") (class "Default")
      (node (ref "R4") (pin "2") (pinfunction "2_2") (pintype "input"))
      (node (ref "R6") (pin "2") (pinfunction "2_2") (pintype "input"))
    )
    (net (code "39") (name "Net-(U3-FB)") (class "Default")
      (node (ref "R5") (pin "1") (pinfunction "1_1") (pintype "input"))
      (node (ref "R6") (pin "1") (pinfunction "1_1") (pintype "input"))
      (node (ref "U3") (pin "3") (pinfunction "FB_3") (pintype "input"))
    )
    (net (code "40") (name "Net-(U4-A1)") (class "Default")
      (node (ref "H1") (pin "5") (pinfunction "5_5") (pintype "input"))
      (node (ref "U4") (pin "2") (pinfunction "A1_2") (pintype "input"))
    )
    (net (code "41") (name "Net-(U4-A2)") (class "Default")
      (node (ref "H1") (pin "4") (pinfunction "4_4") (pintype "input"))
      (node (ref "U4") (pin "3") (pinfunction "A2_3") (pintype "input"))
    )
    (net (code "42") (name "Net-(U4-A3)") (class "Default")
      (node (ref "H1") (pin "3") (pinfunction "3_3") (pintype "input"))
      (node (ref "U4") (pin "4") (pinfunction "A3_4") (pintype "input"))
    )
    (net (code "43") (name "Net-(U4-A4)") (class "Default")
      (node (ref "H1") (pin "2") (pinfunction "2_2") (pintype "input"))
      (node (ref "U4") (pin "5") (pinfunction "A4_5") (pintype "input"))
    )
    (net (code "44") (name "PGND") (class "Default")
      (node (ref "C13") (pin "2") (pinfunction "2_2") (pintype "input"))
      (node (ref "CN1") (pin "1") (pinfunction "-_1") (pintype "input"))
      (node (ref "D4_L1") (pin "2") (pinfunction "A_2") (pintype "input"))
      (node (ref "D4_L2") (pin "2") (pinfunction "A_2") (pintype "input"))
      (node (ref "D4_R1") (pin "2") (pinfunction "A_2") (pintype "input"))
      (node (ref "D4_R2") (pin "2") (pinfunction "A_2") (pintype "input"))
      (node (ref "Q2_L1") (pin "3") (pinfunction "S_3") (pintype "input"))
      (node (ref "Q2_L2") (pin "3") (pinfunction "S_3") (pintype "input"))
      (node (ref "Q2_R1") (pin "3") (pinfunction "S_3") (pintype "input"))
      (node (ref "Q2_R2") (pin "3") (pinfunction "S_3") (pintype "input"))
      (node (ref "R12") (pin "1") (pinfunction "1_1") (pintype "input"))
    )
    (net (code "45") (name "VBAT") (class "Default")
      (node (ref "C1") (pin "2") (pinfunction "2_2") (pintype "input"))
      (node (ref "C10") (pin "2") (pinfunction "2_2") (pintype "input"))
      (node (ref "C2") (pin "2") (pinfunction "2_2") (pintype "input"))
      (node (ref "C9") (pin "2") (pinfunction "2_2") (pintype "input"))
      (node (ref "D3_L1") (pin "1") (pinfunction "C_1") (pintype "input"))
      (node (ref "D3_L2") (pin "1") (pinfunction "C_1") (pintype "input"))
      (node (ref "D3_R1") (pin "1") (pinfunction "C_1") (pintype "input"))
      (node (ref "D3_R2") (pin "1") (pinfunction "C_1") (pintype "input"))
      (node (ref "L1") (pin "2") (pinfunction "2_2") (pintype "input"))
      (node (ref "Q1_L1") (pin "2") (pinfunction "D_2") (pintype "input"))
      (node (ref "Q1_L2") (pin "2") (pinfunction "D_2") (pintype "input"))
      (node (ref "Q1_R1") (pin "2") (pinfunction "D_2") (pintype "input"))
      (node (ref "Q1_R2") (pin "2") (pinfunction "D_2") (pintype "input"))
      (node (ref "U2") (pin "3") (pinfunction "VIN_3") (pintype "input"))
      (node (ref "U3") (pin "4") (pinfunction "EN_4") (pintype "input"))
      (node (ref "U3") (pin "5") (pinfunction "VIN_5") (pintype "input"))
      (node (ref "U5") (pin "2") (pinfunction "2_2") (pintype "input"))
    )
    (net (code "46") (name "unconnected-(U1-VOUT(TAB)-Pad2)") (class "Default")
      (node (ref "U1") (pin "2") (pinfunction "VOUT(TAB)_2") (pintype "input+no_connect"))
    )
    (net (code "47") (name "unconnected-(U2-VOUT(TAB)-Pad2)") (class "Default")
      (node (ref "U2") (pin "2") (pinfunction "VOUT(TAB)_2") (pintype "input+no_connect"))
    )
    (net (code "48") (name "unconnected-(U3-NC-Pad6)") (class "Default")
      (node (ref "U3") (pin "6") (pinfunction "NC_6") (pintype "input+no_connect"))
    )
    (net (code "49") (name "unconnected-(U5-Pad3)") (class "Default")
      (node (ref "U5") (pin "3") (pinfunction "3_3") (pintype "input+no_connect"))
    )
  )
)
